# OXO.net
KiCad netlist of a schematic drawn in EAGLE
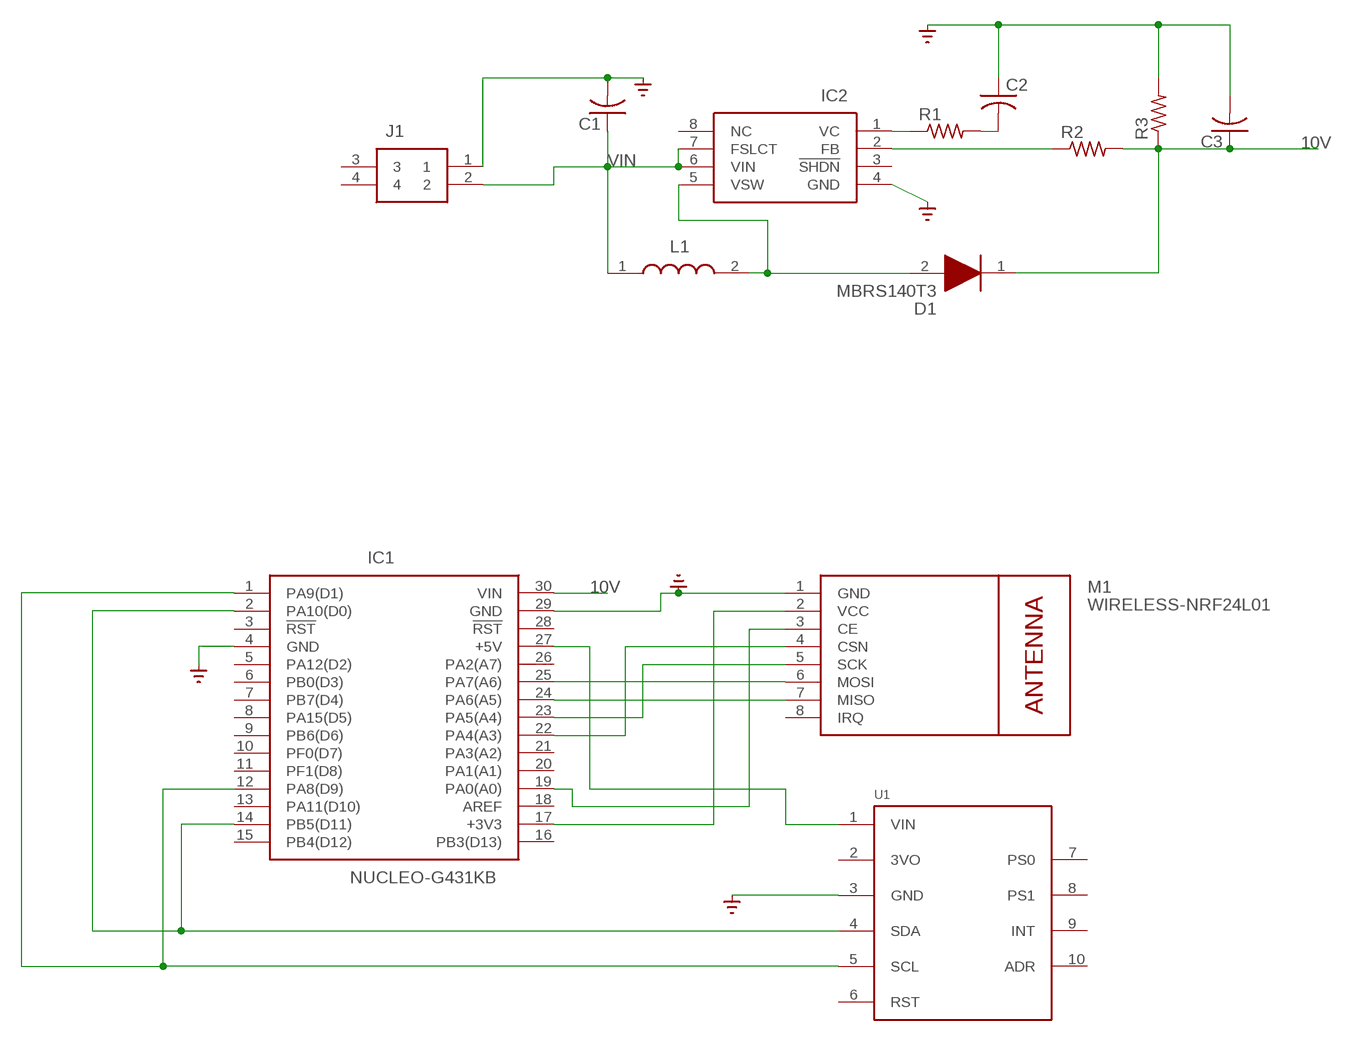
[diagram p0: schematic, sheet 1]

(export (version "E")
  (design (tool "Eeschema 10.0.6"))
  (components
    (comp (ref "C1")
      (value "C-USC1206")
      (footprint "eagle-import:C1206")
      (libsource (lib "eagle-import") (part "C-USC1206"))
    )
    (comp (ref "C2")
      (value "C-USC1206")
      (footprint "eagle-import:C1206")
      (libsource (lib "eagle-import") (part "C-USC1206"))
    )
    (comp (ref "C3")
      (value "C-USC1206")
      (footprint "eagle-import:C1206")
      (libsource (lib "eagle-import") (part "C-USC1206"))
    )
    (comp (ref "D1")
      (value "MBRS140T3")
      (footprint "eagle-import:DIOM5436X247N")
      (fields (field (name "MOUSER_PART_NUMBER") "863-MBRS140T3"))
      (libsource (lib "eagle-import") (part "MBRS140T3"))
    )
    (comp (ref "IC1")
      (value "NUCLEO-G431KB")
      (footprint "eagle-import:DIPS1524W66P254L5029H1500Q30N")
      (fields (field (name "ARROW_PART_NUMBER") "NUCLEO-F303K8") (field (name "RS_PART_NUMBER") "9092862"))
      (libsource (lib "eagle-import") (part "NUCLEO-G431KB"))
    )
    (comp (ref "IC2")
      (value "LM2698MM-ADJ_NOPB")
      (footprint "eagle-import:SOP65P490X110-8N")
      (fields
        (field (name "ARROW_PART_NUMBER") "LM2698MM-ADJ/NOPB")
        (field (name "MOUSER_PART_NUMBER") "926-LM2698MM-ADJNOPB")
      )
      (libsource (lib "eagle-import") (part "LM2698MM-ADJ_NOPB"))
    )
    (comp (ref "J1")
      (value "53398-0271")
      (footprint "eagle-import:533980271")
      (fields (field (name "MOUSER_PART_NUMBER") "538-53398-0271"))
      (libsource (lib "eagle-import") (part "53398-0271"))
    )
    (comp (ref "L1")
      (value "LQH3NPN100MMEL")
      (footprint "eagle-import:LQH3NPN100MMEL")
      (fields (field (name "MOUSER_PART_NUMBER") "81-LQH3NPN100MMEL"))
      (libsource (lib "eagle-import") (part "LQH3NPN100MMEL"))
    )
    (comp (ref "M1")
      (value "WIRELESS-NRF24L01")
      (footprint "eagle-import:WIRELESS-NRF24L01")
      (libsource (lib "eagle-import") (part "WIRELESS-NRF24L01"))
    )
    (comp (ref "R1")
      (value "R-US_R1206")
      (footprint "eagle-import:R1206")
      (libsource (lib "eagle-import") (part "R-US_R1206"))
    )
    (comp (ref "R2")
      (value "R-US_R1206")
      (footprint "eagle-import:R1206")
      (libsource (lib "eagle-import") (part "R-US_R1206"))
    )
    (comp (ref "R3")
      (value "R-US_R1206")
      (footprint "eagle-import:R1206")
      (libsource (lib "eagle-import") (part "R-US_R1206"))
    )
    (comp (ref "U1")
      (value "ADADRUIT-BNO055")
      (footprint "eagle-import:ADAFRUIT-BNO055")
      (libsource (lib "eagle-import") (part "ADADRUIT-BNO055"))
    )
  )
  (nets
    (net (code "1") (name "/3VO") (class "Default")
      (node (ref "U1") (pin "2") (pinfunction "3VO_2") (pintype "power_in"))
    )
    (net (code "2") (name "/10V") (class "Default")
      (node (ref "C3") (pin "1") (pinfunction "1_1") (pintype "passive"))
      (node (ref "D1") (pin "1") (pinfunction "K_1") (pintype "bidirectional"))
      (node (ref "IC1") (pin "30") (pinfunction "VIN_30") (pintype "passive"))
      (node (ref "R2") (pin "2") (pinfunction "2_2") (pintype "passive"))
      (node (ref "R3") (pin "1") (pinfunction "1_1") (pintype "passive"))
    )
    (net (code "3") (name "/VIN") (class "Default")
      (node (ref "C1") (pin "1") (pinfunction "1_1") (pintype "passive"))
      (node (ref "IC2") (pin "6") (pinfunction "VIN_6") (pintype "input"))
      (node (ref "IC2") (pin "7") (pinfunction "FSLCT_7") (pintype "bidirectional"))
      (node (ref "J1") (pin "2") (pinfunction "2_2") (pintype "bidirectional"))
      (node (ref "L1") (pin "1") (pinfunction "1_1") (pintype "bidirectional"))
    )
    (net (code "4") (name "Net-(C2-Pad2)") (class "Default")
      (node (ref "C2") (pin "2") (pinfunction "2_2") (pintype "passive"))
      (node (ref "R1") (pin "2") (pinfunction "2_2") (pintype "passive"))
    )
    (net (code "5") (name "Net-(D1-A)") (class "Default")
      (node (ref "D1") (pin "2") (pinfunction "A_2") (pintype "bidirectional"))
      (node (ref "IC2") (pin "5") (pinfunction "VSW_5") (pintype "bidirectional"))
      (node (ref "L1") (pin "2") (pinfunction "2_2") (pintype "bidirectional"))
    )
    (net (code "6") (name "Net-(IC1-+3V3)") (class "Default")
      (node (ref "IC1") (pin "17") (pinfunction "+3V3_17") (pintype "passive"))
      (node (ref "M1") (pin "2") (pinfunction "VCC_2") (pintype "power_in"))
    )
    (net (code "7") (name "Net-(IC1-+5V)") (class "Default")
      (node (ref "IC1") (pin "27") (pinfunction "+5V_27") (pintype "passive"))
      (node (ref "U1") (pin "1") (pinfunction "VIN_1") (pintype "power_in"))
    )
    (net (code "8") (name "Net-(IC1-PA0(A0))") (class "Default")
      (node (ref "IC1") (pin "19") (pinfunction "PA0(A0)_19") (pintype "bidirectional"))
      (node (ref "M1") (pin "3") (pinfunction "CE_3") (pintype "bidirectional"))
    )
    (net (code "9") (name "Net-(IC1-PA4(A3))") (class "Default")
      (node (ref "IC1") (pin "22") (pinfunction "PA4(A3)_22") (pintype "bidirectional"))
      (node (ref "M1") (pin "4") (pinfunction "CSN_4") (pintype "bidirectional"))
    )
    (net (code "10") (name "Net-(IC1-PA5(A4))") (class "Default")
      (node (ref "IC1") (pin "23") (pinfunction "PA5(A4)_23") (pintype "bidirectional"))
      (node (ref "M1") (pin "5") (pinfunction "SCK_5") (pintype "bidirectional"))
    )
    (net (code "11") (name "Net-(IC1-PA6(A5))") (class "Default")
      (node (ref "IC1") (pin "24") (pinfunction "PA6(A5)_24") (pintype "bidirectional"))
      (node (ref "M1") (pin "7") (pinfunction "MISO_7") (pintype "bidirectional"))
    )
    (net (code "12") (name "Net-(IC1-PA7(A6))") (class "Default")
      (node (ref "IC1") (pin "25") (pinfunction "PA7(A6)_25") (pintype "bidirectional"))
      (node (ref "M1") (pin "6") (pinfunction "MOSI_6") (pintype "bidirectional"))
    )
    (net (code "13") (name "Net-(IC1-PA8(D9))") (class "Default")
      (node (ref "IC1") (pin "1") (pinfunction "PA9(D1)_1") (pintype "bidirectional"))
      (node (ref "IC1") (pin "12") (pinfunction "PA8(D9)_12") (pintype "bidirectional"))
      (node (ref "U1") (pin "5") (pinfunction "SCL_5") (pintype "bidirectional"))
    )
    (net (code "14") (name "Net-(IC1-PA10(D0))") (class "Default")
      (node (ref "IC1") (pin "14") (pinfunction "PB5(D11)_14") (pintype "bidirectional"))
      (node (ref "IC1") (pin "2") (pinfunction "PA10(D0)_2") (pintype "bidirectional"))
      (node (ref "U1") (pin "4") (pinfunction "SDA_4") (pintype "bidirectional"))
    )
    (net (code "15") (name "Net-(IC2-FB)") (class "Default")
      (node (ref "IC2") (pin "2") (pinfunction "FB_2") (pintype "bidirectional"))
      (node (ref "R2") (pin "1") (pinfunction "1_1") (pintype "passive"))
    )
    (net (code "16") (name "Net-(IC2-VC)") (class "Default")
      (node (ref "IC2") (pin "1") (pinfunction "VC_1") (pintype "bidirectional"))
      (node (ref "R1") (pin "1") (pinfunction "1_1") (pintype "passive"))
    )
    (net (code "17") (name "SUPPLY0_GND_") (class "Default")
      (node (ref "C1") (pin "2") (pinfunction "2_2") (pintype "passive"))
      (node (ref "C2") (pin "1") (pinfunction "1_1") (pintype "passive"))
      (node (ref "C3") (pin "2") (pinfunction "2_2") (pintype "passive"))
      (node (ref "IC1") (pin "29") (pinfunction "GND_29") (pintype "passive"))
      (node (ref "IC1") (pin "4") (pinfunction "GND_4") (pintype "passive"))
      (node (ref "IC2") (pin "4") (pinfunction "GND_4") (pintype "power_in"))
      (node (ref "J1") (pin "1") (pinfunction "1_1") (pintype "bidirectional"))
      (node (ref "M1") (pin "1") (pinfunction "GND_1") (pintype "power_in"))
      (node (ref "R3") (pin "2") (pinfunction "2_2") (pintype "passive"))
      (node (ref "U1") (pin "3") (pinfunction "GND_3") (pintype "power_in"))
    )
    (net (code "18") (name "unconnected-(IC1-AREF-Pad18)") (class "Default")
      (node (ref "IC1") (pin "18") (pinfunction "AREF_18") (pintype "passive"))
    )
    (net (code "19") (name "unconnected-(IC1-PA1(A1)-Pad20)") (class "Default")
      (node (ref "IC1") (pin "20") (pinfunction "PA1(A1)_20") (pintype "bidirectional"))
    )
    (net (code "20") (name "unconnected-(IC1-PA2(A7)-Pad26)") (class "Default")
      (node (ref "IC1") (pin "26") (pinfunction "PA2(A7)_26") (pintype "bidirectional"))
    )
    (net (code "21") (name "unconnected-(IC1-PA3(A2)-Pad21)") (class "Default")
      (node (ref "IC1") (pin "21") (pinfunction "PA3(A2)_21") (pintype "bidirectional"))
    )
    (net (code "22") (name "unconnected-(IC1-PA11(D10)-Pad13)") (class "Default")
      (node (ref "IC1") (pin "13") (pinfunction "PA11(D10)_13") (pintype "bidirectional"))
    )
    (net (code "23") (name "unconnected-(IC1-PA12(D2)-Pad5)") (class "Default")
      (node (ref "IC1") (pin "5") (pinfunction "PA12(D2)_5") (pintype "bidirectional"))
    )
    (net (code "24") (name "unconnected-(IC1-PA15(D5)-Pad8)") (class "Default")
      (node (ref "IC1") (pin "8") (pinfunction "PA15(D5)_8") (pintype "bidirectional"))
    )
    (net (code "25") (name "unconnected-(IC1-PB0(D3)-Pad6)") (class "Default")
      (node (ref "IC1") (pin "6") (pinfunction "PB0(D3)_6") (pintype "bidirectional"))
    )
    (net (code "26") (name "unconnected-(IC1-PB3(D13)-Pad16)") (class "Default")
      (node (ref "IC1") (pin "16") (pinfunction "PB3(D13)_16") (pintype "bidirectional"))
    )
    (net (code "27") (name "unconnected-(IC1-PB4(D12)-Pad15)") (class "Default")
      (node (ref "IC1") (pin "15") (pinfunction "PB4(D12)_15") (pintype "bidirectional"))
    )
    (net (code "28") (name "unconnected-(IC1-PB6(D6)-Pad9)") (class "Default")
      (node (ref "IC1") (pin "9") (pinfunction "PB6(D6)_9") (pintype "bidirectional"))
    )
    (net (code "29") (name "unconnected-(IC1-PB7(D4)-Pad7)") (class "Default")
      (node (ref "IC1") (pin "7") (pinfunction "PB7(D4)_7") (pintype "bidirectional"))
    )
    (net (code "30") (name "unconnected-(IC1-PF0(D7)-Pad10)") (class "Default")
      (node (ref "IC1") (pin "10") (pinfunction "PF0(D7)_10") (pintype "bidirectional"))
    )
    (net (code "31") (name "unconnected-(IC1-PF1(D8)-Pad11)") (class "Default")
      (node (ref "IC1") (pin "11") (pinfunction "PF1(D8)_11") (pintype "bidirectional"))
    )
    (net (code "32") (name "unconnected-(IC1-~{RST}-Pad3)") (class "Default")
      (node (ref "IC1") (pin "3") (pinfunction "~{RST}_3") (pintype "bidirectional"))
    )
    (net (code "33") (name "unconnected-(IC1-~{RST}-Pad28)") (class "Default")
      (node (ref "IC1") (pin "28") (pinfunction "~{RST}_28") (pintype "bidirectional"))
    )
    (net (code "34") (name "unconnected-(IC2-NC-Pad8)") (class "Default")
      (node (ref "IC2") (pin "8") (pinfunction "NC_8") (pintype "no_connect"))
    )
    (net (code "35") (name "unconnected-(IC2-~{SHDN}-Pad3)") (class "Default")
      (node (ref "IC2") (pin "3") (pinfunction "~{SHDN}_3") (pintype "bidirectional"))
    )
    (net (code "36") (name "unconnected-(J1-Pad3)") (class "Default")
      (node (ref "J1") (pin "3") (pinfunction "3_3") (pintype "bidirectional"))
    )
    (net (code "37") (name "unconnected-(J1-Pad4)") (class "Default")
      (node (ref "J1") (pin "4") (pinfunction "4_4") (pintype "bidirectional"))
    )
    (net (code "38") (name "unconnected-(M1-IRQ-Pad8)") (class "Default")
      (node (ref "M1") (pin "8") (pinfunction "IRQ_8") (pintype "bidirectional"))
    )
    (net (code "39") (name "unconnected-(U1-ADR-Pad10)") (class "Default")
      (node (ref "U1") (pin "10") (pinfunction "ADR_10") (pintype "bidirectional"))
    )
    (net (code "40") (name "unconnected-(U1-INT-Pad9)") (class "Default")
      (node (ref "U1") (pin "9") (pinfunction "INT_9") (pintype "bidirectional"))
    )
    (net (code "41") (name "unconnected-(U1-PS0-Pad7)") (class "Default")
      (node (ref "U1") (pin "7") (pinfunction "PS0_7") (pintype "bidirectional"))
    )
    (net (code "42") (name "unconnected-(U1-PS1-Pad8)") (class "Default")
      (node (ref "U1") (pin "8") (pinfunction "PS1_8") (pintype "bidirectional"))
    )
    (net (code "43") (name "unconnected-(U1-RST-Pad6)") (class "Default")
      (node (ref "U1") (pin "6") (pinfunction "RST_6") (pintype "bidirectional"))
    )
  )
)
